# ESP32.net
KiCad netlist of a schematic drawn in Altium Designer
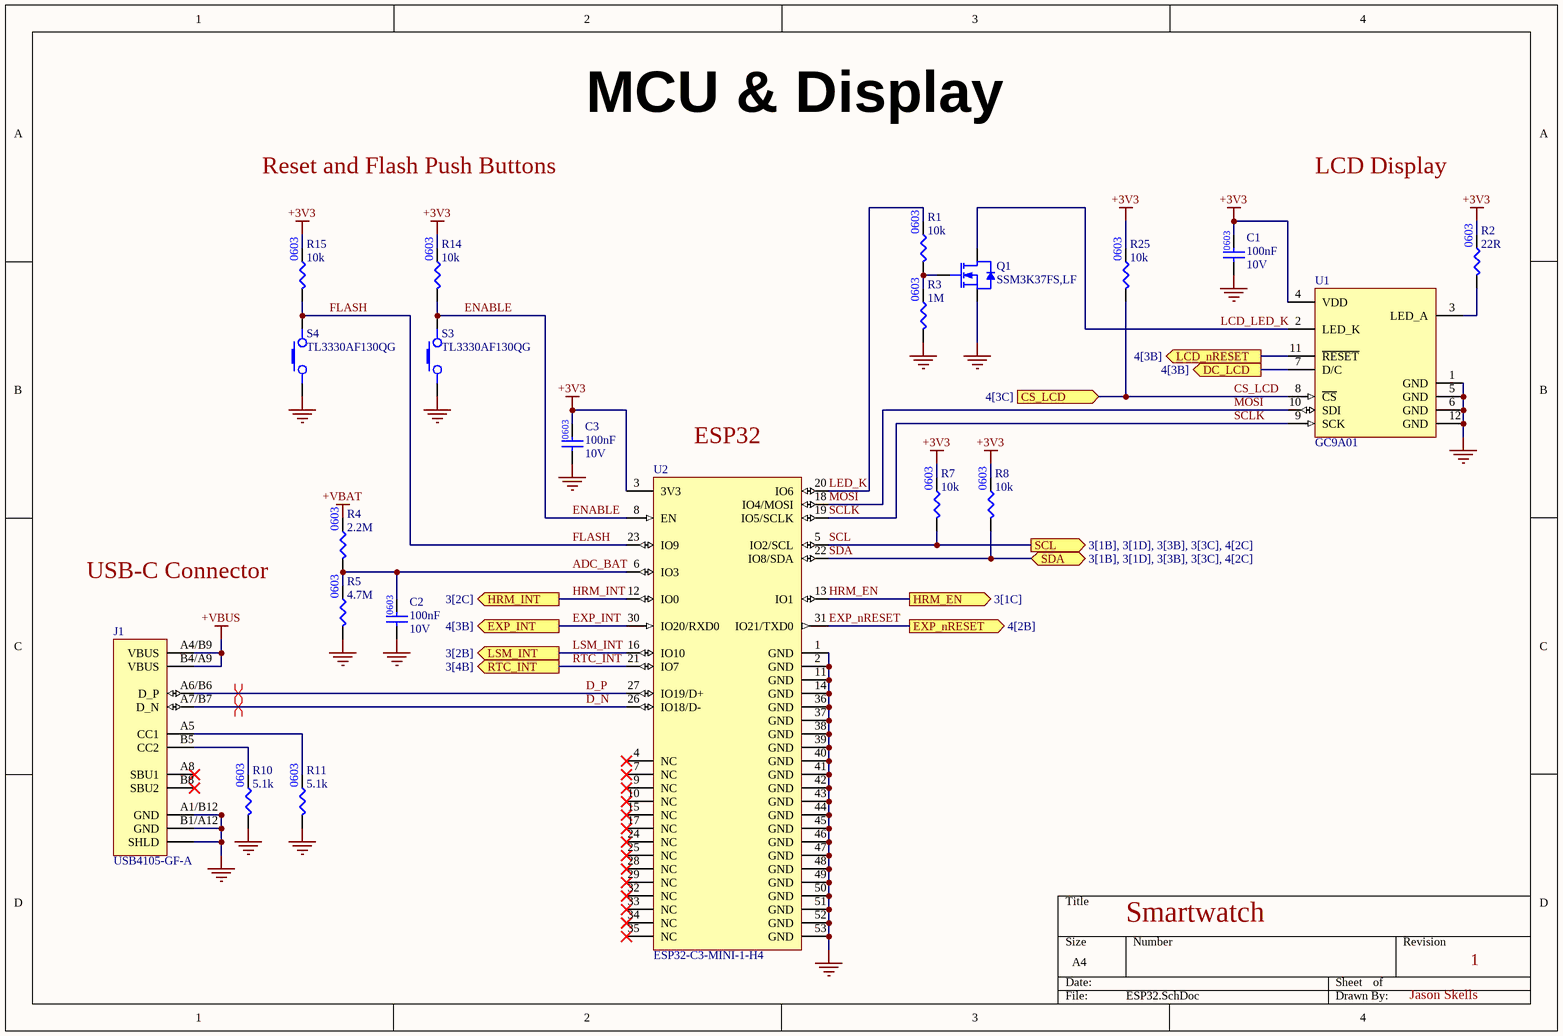
[diagram p0: ESP32.SchDoc]

(export (version "E")
  (design (tool "Eeschema 10.0.6"))
  (components
    (comp (ref "C1")
      (value "CC0603KRX7R6BB104")
      (footprint "CAP_0603")
      (description "CAP CER 0.1UF 10V X7R 0603")
      (fields
        (field (name "MANUFACTURER") "Yageo")
        (field (name "TOLERANCE") "10%")
        (field (name "CAPACITANCE") "100nF")
        (field (name "VOLTAGE RATING") "10V")
      )
      (libsource (lib "Smartwatch_Lib") (part "CC0603KRX7R6BB104"))
    )
    (comp (ref "C2")
      (value "CC0603KRX7R6BB104")
      (footprint "CAP_0603")
      (description "CAP CER 0.1UF 10V X7R 0603")
      (fields
        (field (name "MANUFACTURER") "Yageo")
        (field (name "TOLERANCE") "10%")
        (field (name "CAPACITANCE") "100nF")
        (field (name "VOLTAGE RATING") "10V")
      )
      (libsource (lib "Smartwatch_Lib") (part "CC0603KRX7R6BB104"))
    )
    (comp (ref "C3")
      (value "CC0603KRX7R6BB104")
      (footprint "CAP_0603")
      (description "CAP CER 0.1UF 10V X7R 0603")
      (fields
        (field (name "MANUFACTURER") "Yageo")
        (field (name "TOLERANCE") "10%")
        (field (name "CAPACITANCE") "100nF")
        (field (name "VOLTAGE RATING") "10V")
      )
      (libsource (lib "Smartwatch_Lib") (part "CC0603KRX7R6BB104"))
    )
    (comp (ref "J1")
      (value "USB4105-GF-A")
      (footprint "USB4105-GF-A")
      (description "Conn USB 2.0 Type C RCP 24 POS 0.3mm/0.5mm Solder RA SMD 24 Terminal 1 Port T/R")
      (fields (field (name "MANUFACTURER") "Global Connector Technology"))
      (libsource (lib "Smartwatch_Lib") (part "USB4105-GF-A"))
    )
    (comp (ref "Q1")
      (value "SSM3K37FS,LF")
      (footprint "SSM3K37FS,LF")
      (description "MOSFET NCH 20V 200MA SSM")
      (fields
        (field (name "MANUFACTURER") "Toshiba")
        (field (name "MANUFACTURER PART NUMBER") "SSM3K37FS,LF")
      )
      (libsource (lib "Smartwatch_Lib") (part "SSM3K37FS,LF"))
    )
    (comp (ref "R1")
      (value "RNCP0603FTD10K0")
      (footprint "RES_0603")
      (description "Res Thin Film 0603 10K Ohm 1% 1/8W ±100ppm/°C Molded SMD SMD Paper T/R")
      (fields
        (field (name "MANUFACTURER") "Stackpole Electronics")
        (field (name "TOLERANCE") "1%")
        (field (name "RESISTANCE") "10k")
      )
      (libsource (lib "Smartwatch_Lib") (part "RNCP0603FTD10K0"))
    )
    (comp (ref "R2")
      (value "RC0603FR-0722RL")
      (footprint "RES_0603")
      (description "RES 22 OHM 1% 1/10W 0603")
      (fields
        (field (name "MANUFACTURER") "Yageo")
        (field (name "TOLERANCE") "1%")
        (field (name "RESISTANCE") "22R")
      )
      (libsource (lib "Smartwatch_Lib") (part "RC0603FR-0722RL"))
    )
    (comp (ref "R3")
      (value "RC0603FR-071ML")
      (footprint "RES_0603")
      (description "RES 1M OHM 1% 1/10W 0603")
      (fields
        (field (name "MANUFACTURER") "Yageo")
        (field (name "TOLERANCE") "1%")
        (field (name "RESISTANCE") "1M")
      )
      (libsource (lib "Smartwatch_Lib") (part "RC0603FR-071ML"))
    )
    (comp (ref "R4")
      (value "RC0603FR-072M2L")
      (footprint "RES_0603")
      (description "RES SMD 2.2M OHM 1% 1/10W 0603")
      (fields
        (field (name "MANUFACTURER") "Yageo")
        (field (name "TOLERANCE") "1%")
        (field (name "RESISTANCE") "2.2M")
      )
      (libsource (lib "Smartwatch_Lib") (part "RC0603FR-072M2L"))
    )
    (comp (ref "R5")
      (value "RC0603FR-074M7L")
      (footprint "RES_0603")
      (description "RES 4.7M OHM 1% 1/10W 0603")
      (fields
        (field (name "MANUFACTURER") "Yageo")
        (field (name "TOLERANCE") "1%")
        (field (name "RESISTANCE") "4.7M")
      )
      (libsource (lib "Smartwatch_Lib") (part "RC0603FR-074M7L"))
    )
    (comp (ref "R7")
      (value "RNCP0603FTD10K0")
      (footprint "RES_0603")
      (description "Res Thin Film 0603 10K Ohm 1% 1/8W ±100ppm/°C Molded SMD SMD Paper T/R")
      (fields
        (field (name "MANUFACTURER") "Stackpole Electronics")
        (field (name "TOLERANCE") "1%")
        (field (name "RESISTANCE") "10k")
      )
      (libsource (lib "Smartwatch_Lib") (part "RNCP0603FTD10K0"))
    )
    (comp (ref "R8")
      (value "RNCP0603FTD10K0")
      (footprint "RES_0603")
      (description "Res Thin Film 0603 10K Ohm 1% 1/8W ±100ppm/°C Molded SMD SMD Paper T/R")
      (fields
        (field (name "MANUFACTURER") "Stackpole Electronics")
        (field (name "TOLERANCE") "1%")
        (field (name "RESISTANCE") "10k")
      )
      (libsource (lib "Smartwatch_Lib") (part "RNCP0603FTD10K0"))
    )
    (comp (ref "R10")
      (value "RMCF0603FT5K10")
      (footprint "RES_0603")
      (description "Res Thick Film 0603 5.1K Ohm 1% 0.1W(1/10W) ±100ppm/C Pad SMD Automotive T/R")
      (fields
        (field (name "MANUFACTURER") "Stackpole Electronics")
        (field (name "TOLERANCE") "1%")
        (field (name "RESISTANCE") "5.1k")
      )
      (libsource (lib "Smartwatch_Lib") (part "RMCF0603FT5K10"))
    )
    (comp (ref "R11")
      (value "RMCF0603FT5K10")
      (footprint "RES_0603")
      (description "Res Thick Film 0603 5.1K Ohm 1% 0.1W(1/10W) ±100ppm/C Pad SMD Automotive T/R")
      (fields
        (field (name "MANUFACTURER") "Stackpole Electronics")
        (field (name "TOLERANCE") "1%")
        (field (name "RESISTANCE") "5.1k")
      )
      (libsource (lib "Smartwatch_Lib") (part "RMCF0603FT5K10"))
    )
    (comp (ref "R14")
      (value "RNCP0603FTD10K0")
      (footprint "RES_0603")
      (description "Res Thin Film 0603 10K Ohm 1% 1/8W ±100ppm/°C Molded SMD SMD Paper T/R")
      (fields
        (field (name "MANUFACTURER") "Stackpole Electronics")
        (field (name "TOLERANCE") "1%")
        (field (name "RESISTANCE") "10k")
      )
      (libsource (lib "Smartwatch_Lib") (part "RNCP0603FTD10K0"))
    )
    (comp (ref "R15")
      (value "RNCP0603FTD10K0")
      (footprint "RES_0603")
      (description "Res Thin Film 0603 10K Ohm 1% 1/8W ±100ppm/°C Molded SMD SMD Paper T/R")
      (fields
        (field (name "MANUFACTURER") "Stackpole Electronics")
        (field (name "TOLERANCE") "1%")
        (field (name "RESISTANCE") "10k")
      )
      (libsource (lib "Smartwatch_Lib") (part "RNCP0603FTD10K0"))
    )
    (comp (ref "R25")
      (value "RNCP0603FTD10K0")
      (footprint "RES_0603")
      (description "Res Thin Film 0603 10K Ohm 1% 1/8W ±100ppm/°C Molded SMD SMD Paper T/R")
      (fields
        (field (name "MANUFACTURER") "Stackpole Electronics")
        (field (name "TOLERANCE") "1%")
        (field (name "RESISTANCE") "10k")
      )
      (libsource (lib "Smartwatch_Lib") (part "RNCP0603FTD10K0"))
    )
    (comp (ref "S3")
      (value "TL3330AF130QG")
      (footprint "TL3330AF130QG")
      (description "Switch Tactile N.O. SPST Rectangular Button Gull Wing 0.05A 12VDC 50000Cycles 1.27N SMD T/R")
      (fields
        (field (name "MANUFACTURER") "E-Switch")
        (field (name "MANUFACTURER PART NUMBER") "TL3330AF130QG")
      )
      (libsource (lib "Smartwatch_Lib") (part "TL3330AF130QG"))
    )
    (comp (ref "S4")
      (value "TL3330AF130QG")
      (footprint "TL3330AF130QG")
      (description "Switch Tactile N.O. SPST Rectangular Button Gull Wing 0.05A 12VDC 50000Cycles 1.27N SMD T/R")
      (fields
        (field (name "MANUFACTURER") "E-Switch")
        (field (name "MANUFACTURER PART NUMBER") "TL3330AF130QG")
      )
      (libsource (lib "Smartwatch_Lib") (part "TL3330AF130QG"))
    )
    (comp (ref "U1")
      (value "GC9A01")
      (footprint "GC9A01")
      (description "GC9A01 LCD Display")
      (libsource (lib "Smartwatch_Lib") (part "GC9A01"))
    )
    (comp (ref "U2")
      (value "ESP32-C3-MINI-1-H4")
      (footprint "ESP32-C3-MINI-1-H4")
      (description "SMD Module, ESP32-C3FH4, Pcb Ant")
      (fields (field (name "MANUFACTURER") "Espressif Systems"))
      (libsource (lib "Smartwatch_Lib") (part "ESP32-C3-MINI-1-H4"))
    )
  )
  (nets
    (net (code "1") (name "+3V3") (class "Default")
      (node (ref "C1") (pin "2") (pinfunction "2_2") (pintype "passive"))
      (node (ref "C3") (pin "2") (pinfunction "2_2") (pintype "passive"))
      (node (ref "R14") (pin "2") (pinfunction "2_2") (pintype "passive"))
      (node (ref "R15") (pin "2") (pinfunction "2_2") (pintype "passive"))
      (node (ref "R2") (pin "2") (pinfunction "2_2") (pintype "passive"))
      (node (ref "R25") (pin "2") (pinfunction "2_2") (pintype "passive"))
      (node (ref "R7") (pin "2") (pinfunction "2_2") (pintype "passive"))
      (node (ref "R8") (pin "2") (pinfunction "2_2") (pintype "passive"))
      (node (ref "U1") (pin "4") (pinfunction "VDD_4") (pintype "passive"))
      (node (ref "U2") (pin "3") (pinfunction "3V3_3") (pintype "power_in"))
    )
    (net (code "2") (name "+VBAT") (class "Default")
      (node (ref "R4") (pin "2") (pinfunction "2_2") (pintype "passive"))
    )
    (net (code "3") (name "+VBUS") (class "Default")
      (node (ref "J1") (pin "A4/B9") (pinfunction "VBUS_A4/B9") (pintype "power_in"))
      (node (ref "J1") (pin "B4/A9") (pinfunction "VBUS_B4/A9") (pintype "power_in"))
    )
    (net (code "4") (name "/ADC_BAT") (class "Default")
      (node (ref "C2") (pin "2") (pinfunction "2_2") (pintype "passive"))
      (node (ref "R4") (pin "1") (pinfunction "1_1") (pintype "passive"))
      (node (ref "R5") (pin "2") (pinfunction "2_2") (pintype "passive"))
      (node (ref "U2") (pin "6") (pinfunction "IO3_6") (pintype "bidirectional"))
    )
    (net (code "5") (name "/CS_LCD") (class "Default")
      (node (ref "R25") (pin "1") (pinfunction "1_1") (pintype "passive"))
      (node (ref "U1") (pin "8") (pinfunction "~{CS}_8") (pintype "input"))
    )
    (net (code "6") (name "/DC_LCD") (class "Default")
      (node (ref "U1") (pin "7") (pinfunction "D/C_7") (pintype "passive"))
    )
    (net (code "7") (name "/D_N") (class "Default")
      (node (ref "J1") (pin "A7/B7") (pinfunction "D_N_A7/B7") (pintype "bidirectional"))
      (node (ref "U2") (pin "26") (pinfunction "IO18/D-_26") (pintype "bidirectional"))
    )
    (net (code "8") (name "/D_P") (class "Default")
      (node (ref "J1") (pin "A6/B6") (pinfunction "D_P_A6/B6") (pintype "bidirectional"))
      (node (ref "U2") (pin "27") (pinfunction "IO19/D+_27") (pintype "bidirectional"))
    )
    (net (code "9") (name "/ENABLE") (class "Default")
      (node (ref "R14") (pin "1") (pinfunction "1_1") (pintype "passive"))
      (node (ref "S3") (pin "1") (pintype "passive"))
      (node (ref "U2") (pin "8") (pinfunction "EN_8") (pintype "input"))
    )
    (net (code "10") (name "/EXP_INT") (class "Default")
      (node (ref "U2") (pin "30") (pinfunction "IO20/RXD0_30") (pintype "input"))
    )
    (net (code "11") (name "/EXP_nRESET") (class "Default")
      (node (ref "U2") (pin "31") (pinfunction "IO21/TXD0_31") (pintype "output"))
    )
    (net (code "12") (name "/FLASH") (class "Default")
      (node (ref "R15") (pin "1") (pinfunction "1_1") (pintype "passive"))
      (node (ref "S4") (pin "1") (pintype "passive"))
      (node (ref "U2") (pin "23") (pinfunction "IO9_23") (pintype "bidirectional"))
    )
    (net (code "13") (name "/HRM_EN") (class "Default")
      (node (ref "U2") (pin "13") (pinfunction "IO1_13") (pintype "bidirectional"))
    )
    (net (code "14") (name "/HRM_INT") (class "Default")
      (node (ref "U2") (pin "12") (pinfunction "IO0_12") (pintype "bidirectional"))
    )
    (net (code "15") (name "/LCD_LED_K") (class "Default")
      (node (ref "Q1") (pin "1") (pinfunction "Drain_1") (pintype "passive"))
      (node (ref "U1") (pin "2") (pinfunction "LED_K_2") (pintype "passive"))
    )
    (net (code "16") (name "/LCD_nRESET") (class "Default")
      (node (ref "U1") (pin "11") (pinfunction "~{RESET}_11") (pintype "passive"))
    )
    (net (code "17") (name "/LED_K") (class "Default")
      (node (ref "R1") (pin "2") (pinfunction "2_2") (pintype "passive"))
      (node (ref "U2") (pin "20") (pinfunction "IO6_20") (pintype "bidirectional"))
    )
    (net (code "18") (name "/LSM_INT") (class "Default")
      (node (ref "U2") (pin "16") (pinfunction "IO10_16") (pintype "bidirectional"))
    )
    (net (code "19") (name "/MOSI") (class "Default")
      (node (ref "U1") (pin "10") (pinfunction "SDI_10") (pintype "bidirectional"))
      (node (ref "U2") (pin "18") (pinfunction "IO4/MOSI_18") (pintype "bidirectional"))
    )
    (net (code "20") (name "/RTC_INT") (class "Default")
      (node (ref "U2") (pin "21") (pinfunction "IO7_21") (pintype "bidirectional"))
    )
    (net (code "21") (name "/SCL") (class "Default")
      (node (ref "R7") (pin "1") (pinfunction "1_1") (pintype "passive"))
      (node (ref "U2") (pin "5") (pinfunction "IO2/SCL_5") (pintype "bidirectional"))
    )
    (net (code "22") (name "/SCLK") (class "Default")
      (node (ref "U1") (pin "9") (pinfunction "SCK_9") (pintype "input"))
      (node (ref "U2") (pin "19") (pinfunction "IO5/SCLK_19") (pintype "bidirectional"))
    )
    (net (code "23") (name "/SDA") (class "Default")
      (node (ref "R8") (pin "1") (pinfunction "1_1") (pintype "passive"))
      (node (ref "U2") (pin "22") (pinfunction "IO8/SDA_22") (pintype "bidirectional"))
    )
    (net (code "24") (name "GND") (class "Default")
      (node (ref "C1") (pin "1") (pinfunction "1_1") (pintype "passive"))
      (node (ref "C2") (pin "1") (pinfunction "1_1") (pintype "passive"))
      (node (ref "C3") (pin "1") (pinfunction "1_1") (pintype "passive"))
      (node (ref "J1") (pin "A1/B12") (pinfunction "GND_A1/B12") (pintype "power_in"))
      (node (ref "J1") (pin "B1/A12") (pinfunction "GND_B1/A12") (pintype "power_in"))
      (node (ref "J1") (pin "SHLD") (pinfunction "SHLD_SHLD") (pintype "power_in"))
      (node (ref "Q1") (pin "3") (pinfunction "Source_3") (pintype "passive"))
      (node (ref "R10") (pin "1") (pinfunction "1_1") (pintype "passive"))
      (node (ref "R11") (pin "1") (pinfunction "1_1") (pintype "passive"))
      (node (ref "R3") (pin "1") (pinfunction "1_1") (pintype "passive"))
      (node (ref "R5") (pin "1") (pinfunction "1_1") (pintype "passive"))
      (node (ref "S3") (pin "2") (pintype "passive"))
      (node (ref "S4") (pin "2") (pintype "passive"))
      (node (ref "U1") (pin "1") (pinfunction "GND_1") (pintype "passive"))
      (node (ref "U1") (pin "12") (pinfunction "GND_12") (pintype "passive"))
      (node (ref "U1") (pin "5") (pinfunction "GND_5") (pintype "passive"))
      (node (ref "U1") (pin "6") (pinfunction "GND_6") (pintype "passive"))
      (node (ref "U2") (pin "1") (pinfunction "GND_1") (pintype "power_in"))
      (node (ref "U2") (pin "11") (pinfunction "GND_11") (pintype "power_in"))
      (node (ref "U2") (pin "14") (pinfunction "GND_14") (pintype "power_in"))
      (node (ref "U2") (pin "2") (pinfunction "GND_2") (pintype "power_in"))
      (node (ref "U2") (pin "36") (pinfunction "GND_36") (pintype "power_in"))
      (node (ref "U2") (pin "37") (pinfunction "GND_37") (pintype "power_in"))
      (node (ref "U2") (pin "38") (pinfunction "GND_38") (pintype "power_in"))
      (node (ref "U2") (pin "39") (pinfunction "GND_39") (pintype "power_in"))
      (node (ref "U2") (pin "40") (pinfunction "GND_40") (pintype "power_in"))
      (node (ref "U2") (pin "41") (pinfunction "GND_41") (pintype "power_in"))
      (node (ref "U2") (pin "42") (pinfunction "GND_42") (pintype "power_in"))
      (node (ref "U2") (pin "43") (pinfunction "GND_43") (pintype "power_in"))
      (node (ref "U2") (pin "44") (pinfunction "GND_44") (pintype "power_in"))
      (node (ref "U2") (pin "45") (pinfunction "GND_45") (pintype "power_in"))
      (node (ref "U2") (pin "46") (pinfunction "GND_46") (pintype "power_in"))
      (node (ref "U2") (pin "47") (pinfunction "GND_47") (pintype "power_in"))
      (node (ref "U2") (pin "48") (pinfunction "GND_48") (pintype "power_in"))
      (node (ref "U2") (pin "49") (pinfunction "GND_49") (pintype "power_in"))
      (node (ref "U2") (pin "50") (pinfunction "GND_50") (pintype "power_in"))
      (node (ref "U2") (pin "51") (pinfunction "GND_51") (pintype "power_in"))
      (node (ref "U2") (pin "52") (pinfunction "GND_52") (pintype "power_in"))
      (node (ref "U2") (pin "53") (pinfunction "GND_53") (pintype "power_in"))
    )
    (net (code "25") (name "Net-(J1-CC1)") (class "Default")
      (node (ref "J1") (pin "A5") (pinfunction "CC1_A5") (pintype "passive"))
      (node (ref "R11") (pin "2") (pinfunction "2_2") (pintype "passive"))
    )
    (net (code "26") (name "Net-(J1-CC2)") (class "Default")
      (node (ref "J1") (pin "B5") (pinfunction "CC2_B5") (pintype "passive"))
      (node (ref "R10") (pin "2") (pinfunction "2_2") (pintype "passive"))
    )
    (net (code "27") (name "Net-(Q1-Gate)") (class "Default")
      (node (ref "Q1") (pin "2") (pinfunction "Gate_2") (pintype "passive"))
      (node (ref "R1") (pin "1") (pinfunction "1_1") (pintype "passive"))
      (node (ref "R3") (pin "2") (pinfunction "2_2") (pintype "passive"))
    )
    (net (code "28") (name "Net-(U1-LED_A)") (class "Default")
      (node (ref "R2") (pin "1") (pinfunction "1_1") (pintype "passive"))
      (node (ref "U1") (pin "3") (pinfunction "LED_A_3") (pintype "passive"))
    )
    (net (code "29") (name "unconnected-(J1-SBU1-PadA8)") (class "Default")
      (node (ref "J1") (pin "A8") (pinfunction "SBU1_A8") (pintype "passive+no_connect"))
    )
    (net (code "30") (name "unconnected-(J1-SBU2-PadB8)") (class "Default")
      (node (ref "J1") (pin "B8") (pinfunction "SBU2_B8") (pintype "passive+no_connect"))
    )
    (net (code "31") (name "unconnected-(U2-NC-Pad4)") (class "Default")
      (node (ref "U2") (pin "4") (pinfunction "NC_4") (pintype "passive+no_connect"))
    )
    (net (code "32") (name "unconnected-(U2-NC-Pad7)") (class "Default")
      (node (ref "U2") (pin "7") (pinfunction "NC_7") (pintype "passive+no_connect"))
    )
    (net (code "33") (name "unconnected-(U2-NC-Pad9)") (class "Default")
      (node (ref "U2") (pin "9") (pinfunction "NC_9") (pintype "passive+no_connect"))
    )
    (net (code "34") (name "unconnected-(U2-NC-Pad10)") (class "Default")
      (node (ref "U2") (pin "10") (pinfunction "NC_10") (pintype "passive+no_connect"))
    )
    (net (code "35") (name "unconnected-(U2-NC-Pad15)") (class "Default")
      (node (ref "U2") (pin "15") (pinfunction "NC_15") (pintype "passive+no_connect"))
    )
    (net (code "36") (name "unconnected-(U2-NC-Pad17)") (class "Default")
      (node (ref "U2") (pin "17") (pinfunction "NC_17") (pintype "passive+no_connect"))
    )
    (net (code "37") (name "unconnected-(U2-NC-Pad24)") (class "Default")
      (node (ref "U2") (pin "24") (pinfunction "NC_24") (pintype "passive+no_connect"))
    )
    (net (code "38") (name "unconnected-(U2-NC-Pad25)") (class "Default")
      (node (ref "U2") (pin "25") (pinfunction "NC_25") (pintype "passive+no_connect"))
    )
    (net (code "39") (name "unconnected-(U2-NC-Pad28)") (class "Default")
      (node (ref "U2") (pin "28") (pinfunction "NC_28") (pintype "passive+no_connect"))
    )
    (net (code "40") (name "unconnected-(U2-NC-Pad29)") (class "Default")
      (node (ref "U2") (pin "29") (pinfunction "NC_29") (pintype "passive+no_connect"))
    )
    (net (code "41") (name "unconnected-(U2-NC-Pad32)") (class "Default")
      (node (ref "U2") (pin "32") (pinfunction "NC_32") (pintype "passive+no_connect"))
    )
    (net (code "42") (name "unconnected-(U2-NC-Pad33)") (class "Default")
      (node (ref "U2") (pin "33") (pinfunction "NC_33") (pintype "passive+no_connect"))
    )
    (net (code "43") (name "unconnected-(U2-NC-Pad34)") (class "Default")
      (node (ref "U2") (pin "34") (pinfunction "NC_34") (pintype "passive+no_connect"))
    )
    (net (code "44") (name "unconnected-(U2-NC-Pad35)") (class "Default")
      (node (ref "U2") (pin "35") (pinfunction "NC_35") (pintype "passive+no_connect"))
    )
  )
)
